# recever.net
KiCad netlist of a schematic drawn in EAGLE
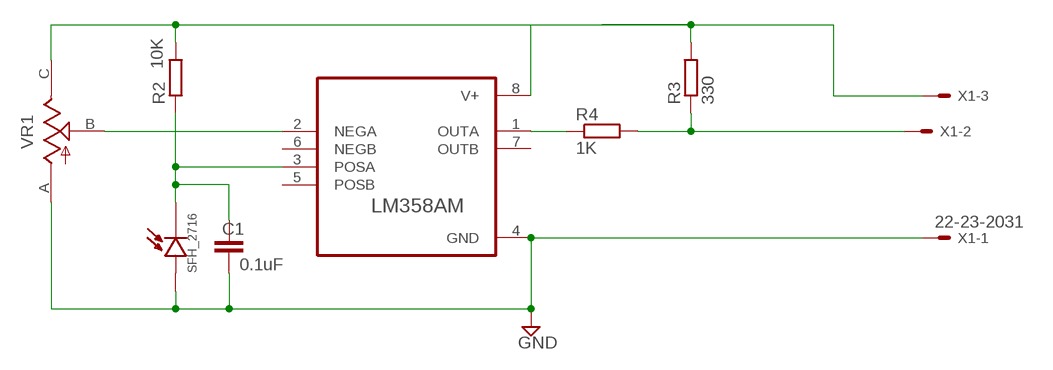
[diagram p0: schematic, sheet 1]

(export (version "E")
  (design (tool "Eeschema 10.0.6"))
  (components
    (comp (ref "C1")
      (value "0.1uF")
      (footprint "eagle-import:C1206")
      (libsource (lib "eagle-import") (part "C-EUC1206"))
    )
    (comp (ref "D1")
      (value "SFH_2716")
      (footprint "eagle-import:LEDC2012X100N")
      (fields (field (name "MF") "OSRAM Opto") (field (name "MP") "SFH 2716"))
      (libsource (lib "eagle-import") (part "SFH_2716"))
    )
    (comp (ref "R2")
      (value "10K")
      (footprint "eagle-import:R1206")
      (libsource (lib "eagle-import") (part "R-EU_R1206"))
    )
    (comp (ref "R3")
      (value "330")
      (footprint "eagle-import:R1206")
      (libsource (lib "eagle-import") (part "R-EU_R1206"))
    )
    (comp (ref "R4")
      (value "1K")
      (footprint "eagle-import:R1206")
      (libsource (lib "eagle-import") (part "R-EU_R1206"))
    )
    (comp (ref "U1")
      (value "LM358AM")
      (footprint "eagle-import:SOIC127P599X175-8N")
      (fields (field (name "MF") "Texas Instruments"))
      (libsource (lib "eagle-import") (part "LM358AM"))
    )
    (comp (ref "VR1")
      (value "10K")
      (footprint "eagle-import:TRIM_TS53YJ103MR10")
      (fields (field (name "MF") "Vishay") (field (name "MP") "TS53YJ103MR10"))
      (libsource (lib "eagle-import") (part "TS53YJ103MR10"))
    )
    (comp (ref "X1")
      (value "22-23-2031")
      (footprint "eagle-import:22-23-2031")
      (fields (field (name "MF") "MOLEX"))
      (libsource (lib "eagle-import") (part "22-23-2031"))
    )
  )
  (nets
    (net (code "1") (name "GND") (class "Default")
      (node (ref "C1") (pin "2") (pinfunction "2_2") (pintype "passive"))
      (node (ref "D1") (pin "A") (pinfunction "A_A") (pintype "passive"))
      (node (ref "U1") (pin "4") (pinfunction "GND_4") (pintype "power_in"))
      (node (ref "VR1") (pin "A") (pinfunction "A_A") (pintype "passive"))
      (node (ref "X1") (pin "1") (pinfunction "S_1") (pintype "passive"))
    )
    (net (code "2") (name "Net-(U1-NEGA)") (class "Default")
      (node (ref "U1") (pin "2") (pinfunction "NEGA_2") (pintype "input"))
      (node (ref "VR1") (pin "B") (pinfunction "B_B") (pintype "passive"))
    )
    (net (code "3") (name "Net-(U1-OUTA)") (class "Default")
      (node (ref "R4") (pin "1") (pinfunction "1_1") (pintype "passive"))
      (node (ref "U1") (pin "1") (pinfunction "OUTA_1") (pintype "output"))
    )
    (net (code "4") (name "Net-(U1-POSA)") (class "Default")
      (node (ref "C1") (pin "1") (pinfunction "1_1") (pintype "passive"))
      (node (ref "D1") (pin "C") (pinfunction "C_C") (pintype "passive"))
      (node (ref "R2") (pin "1") (pinfunction "1_1") (pintype "passive"))
      (node (ref "U1") (pin "3") (pinfunction "POSA_3") (pintype "input"))
    )
    (net (code "5") (name "Net-(U1-V+)") (class "Default")
      (node (ref "R2") (pin "2") (pinfunction "2_2") (pintype "passive"))
      (node (ref "R3") (pin "2") (pinfunction "2_2") (pintype "passive"))
      (node (ref "U1") (pin "8") (pinfunction "V+_8") (pintype "power_in"))
      (node (ref "VR1") (pin "C") (pinfunction "C_C") (pintype "passive"))
      (node (ref "X1") (pin "3") (pinfunction "S_3") (pintype "passive"))
    )
    (net (code "6") (name "Net-(X1B-S)") (class "Default")
      (node (ref "R3") (pin "1") (pinfunction "1_1") (pintype "passive"))
      (node (ref "R4") (pin "2") (pinfunction "2_2") (pintype "passive"))
      (node (ref "X1") (pin "2") (pinfunction "S_2") (pintype "passive"))
    )
    (net (code "7") (name "unconnected-(U1-NEGB-Pad6)") (class "Default")
      (node (ref "U1") (pin "6") (pinfunction "NEGB_6") (pintype "input"))
    )
    (net (code "8") (name "unconnected-(U1-OUTB-Pad7)") (class "Default")
      (node (ref "U1") (pin "7") (pinfunction "OUTB_7") (pintype "output"))
    )
    (net (code "9") (name "unconnected-(U1-POSB-Pad5)") (class "Default")
      (node (ref "U1") (pin "5") (pinfunction "POSB_5") (pintype "input"))
    )
  )
)
